# APU.net
KiCad netlist of a schematic drawn in EAGLE
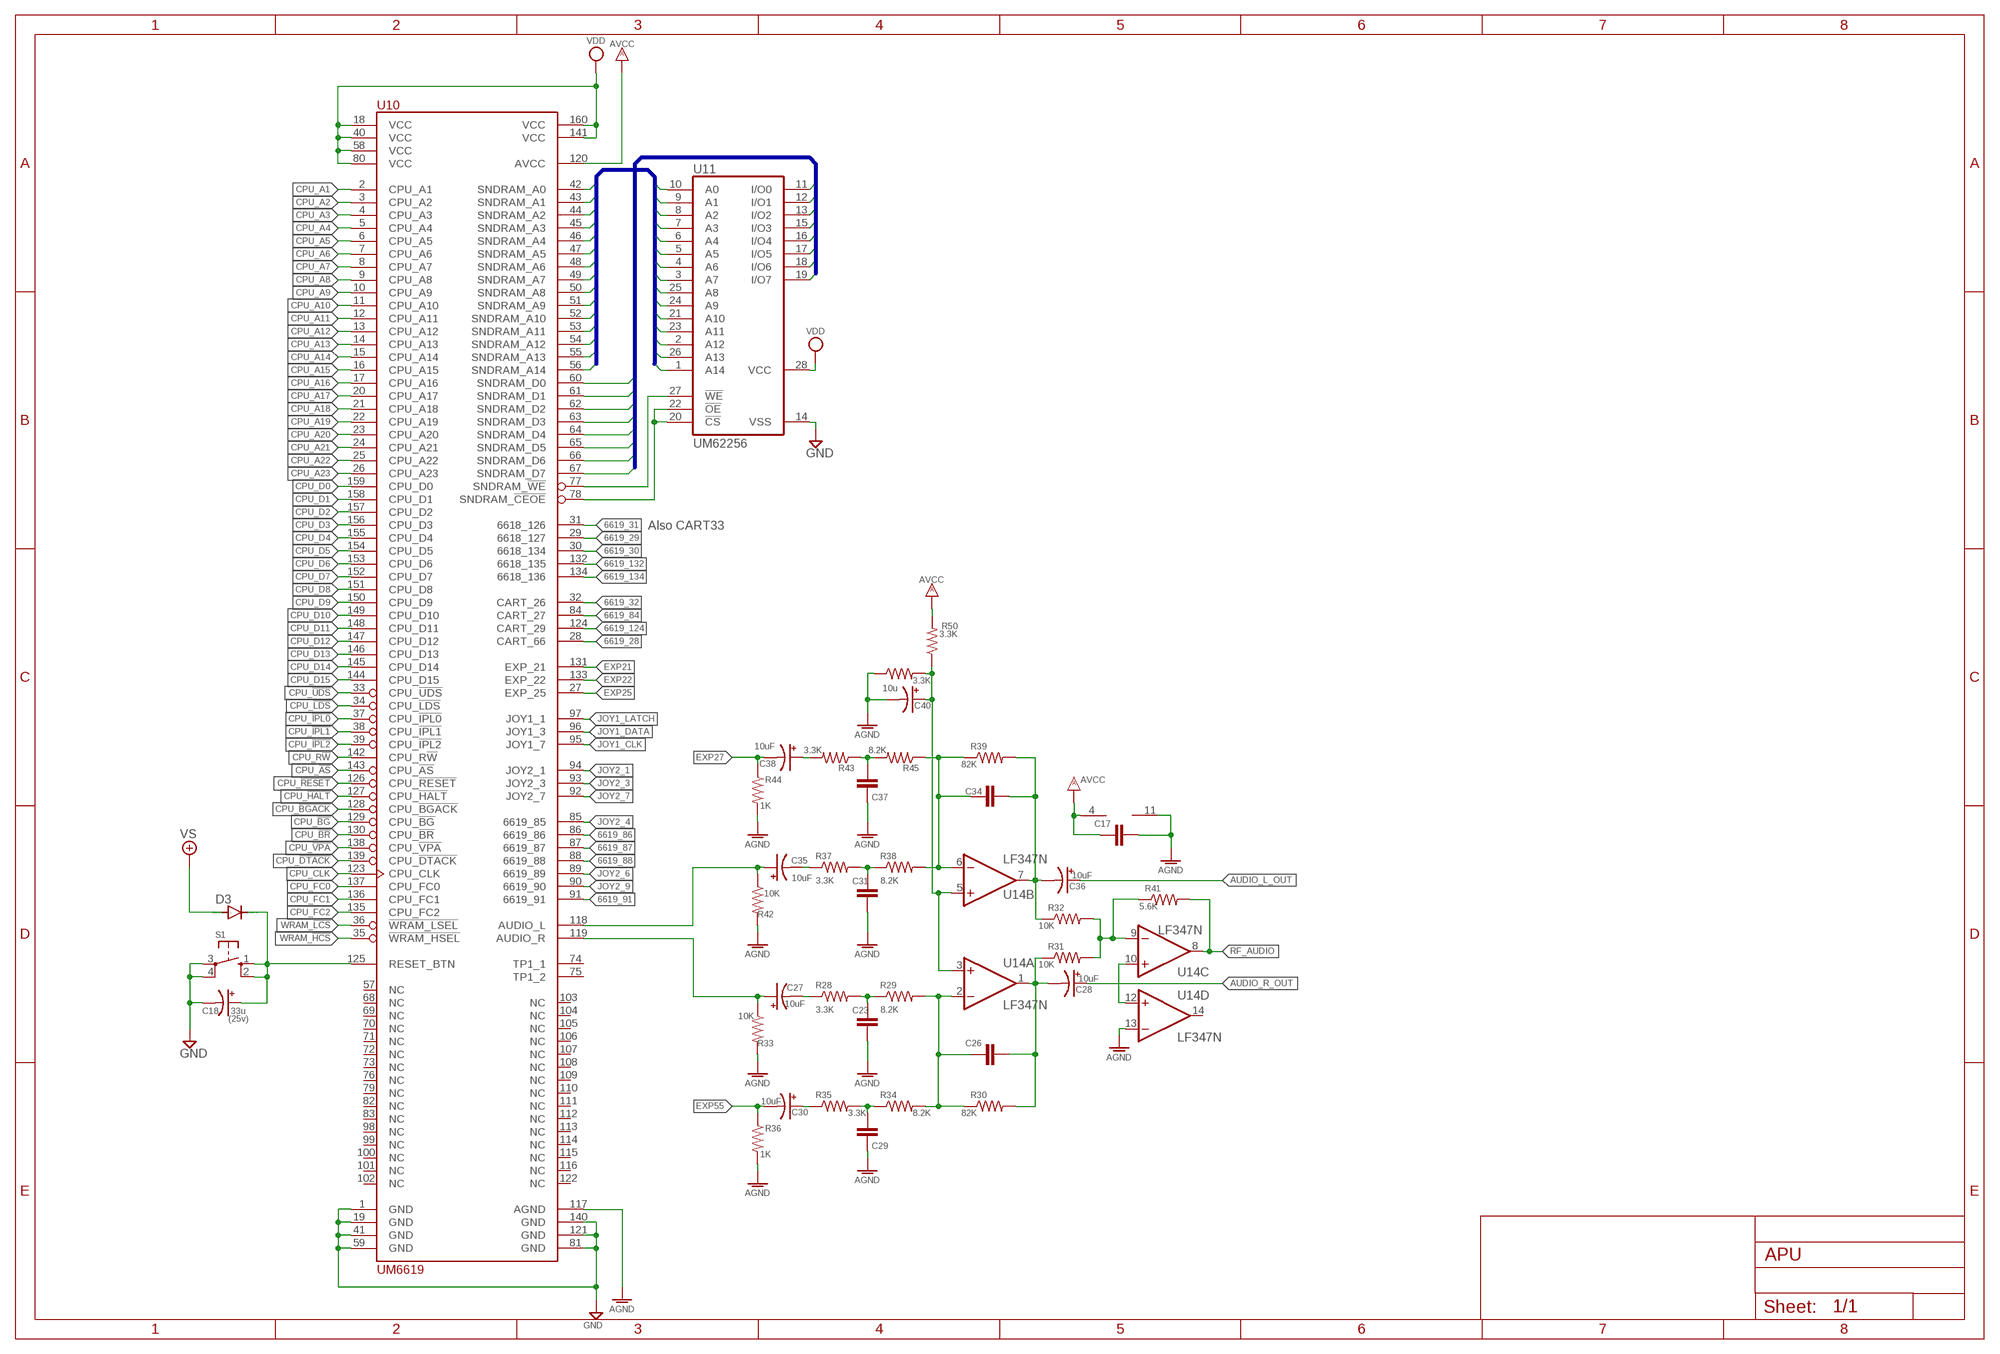
[diagram p0: schematic, sheet 1]

(export (version "E")
  (design (tool "Eeschema 10.0.6"))
  (components
    (comp (ref "C17")
      (value "C-EUC0805")
      (footprint "eagle-import:C0805")
      (libsource (lib "eagle-import") (part "C-EUC0805"))
    )
    (comp (ref "C18")
      (value "33u")
      (footprint "eagle-import:E2,5-5")
      (libsource (lib "eagle-import") (part "CPOL-USE2.5-5"))
    )
    (comp (ref "C23")
      (value "C-EUC0805")
      (footprint "eagle-import:C0805")
      (libsource (lib "eagle-import") (part "C-EUC0805"))
    )
    (comp (ref "C26")
      (value "C-EUC0805")
      (footprint "eagle-import:C0805")
      (libsource (lib "eagle-import") (part "C-EUC0805"))
    )
    (comp (ref "C27")
      (value "10uF")
      (footprint "eagle-import:TAP5-50")
      (libsource (lib "eagle-import") (part "CPOL-USTAP5-50"))
    )
    (comp (ref "C28")
      (value "10uF")
      (footprint "eagle-import:TAP5-50")
      (libsource (lib "eagle-import") (part "CPOL-USTAP5-50"))
    )
    (comp (ref "C29")
      (value "C-EUC0805")
      (footprint "eagle-import:C0805")
      (libsource (lib "eagle-import") (part "C-EUC0805"))
    )
    (comp (ref "C30")
      (value "10uF")
      (footprint "eagle-import:TAP5-50")
      (libsource (lib "eagle-import") (part "CPOL-USTAP5-50"))
    )
    (comp (ref "C31")
      (value "C-EUC0805")
      (footprint "eagle-import:C0805")
      (libsource (lib "eagle-import") (part "C-EUC0805"))
    )
    (comp (ref "C34")
      (value "C-EUC0805")
      (footprint "eagle-import:C0805")
      (libsource (lib "eagle-import") (part "C-EUC0805"))
    )
    (comp (ref "C35")
      (value "10uF")
      (footprint "eagle-import:TAP5-50")
      (libsource (lib "eagle-import") (part "CPOL-USTAP5-50"))
    )
    (comp (ref "C36")
      (value "10uF")
      (footprint "eagle-import:TAP5-50")
      (libsource (lib "eagle-import") (part "CPOL-USTAP5-50"))
    )
    (comp (ref "C37")
      (value "C-EUC0805")
      (footprint "eagle-import:C0805")
      (libsource (lib "eagle-import") (part "C-EUC0805"))
    )
    (comp (ref "C38")
      (value "10uF")
      (footprint "eagle-import:TAP5-50")
      (libsource (lib "eagle-import") (part "CPOL-USTAP5-50"))
    )
    (comp (ref "C40")
      (value "10u")
      (footprint "eagle-import:TAP5-50")
      (libsource (lib "eagle-import") (part "CPOL-USTAP5-50"))
    )
    (comp (ref "D3")
      (value "DIODE-SOD80C")
      (footprint "eagle-import:SOD80C")
      (libsource (lib "eagle-import") (part "DIODE-SOD80C"))
    )
    (comp (ref "R28")
      (value "3.3K")
      (footprint "eagle-import:R0805")
      (libsource (lib "eagle-import") (part "R-US_R0805"))
    )
    (comp (ref "R29")
      (value "8.2K")
      (footprint "eagle-import:R0805")
      (libsource (lib "eagle-import") (part "R-US_R0805"))
    )
    (comp (ref "R30")
      (value "82K")
      (footprint "eagle-import:R0805")
      (libsource (lib "eagle-import") (part "R-US_R0805"))
    )
    (comp (ref "R31")
      (value "10K")
      (footprint "eagle-import:R0805")
      (libsource (lib "eagle-import") (part "R-US_R0805"))
    )
    (comp (ref "R32")
      (value "10K")
      (footprint "eagle-import:R0805")
      (libsource (lib "eagle-import") (part "R-US_R0805"))
    )
    (comp (ref "R33")
      (value "10K")
      (footprint "eagle-import:R0805")
      (libsource (lib "eagle-import") (part "R-US_R0805"))
    )
    (comp (ref "R34")
      (value "8.2K")
      (footprint "eagle-import:R0805")
      (libsource (lib "eagle-import") (part "R-US_R0805"))
    )
    (comp (ref "R35")
      (value "3.3K")
      (footprint "eagle-import:R0805")
      (libsource (lib "eagle-import") (part "R-US_R0805"))
    )
    (comp (ref "R36")
      (value "1K")
      (footprint "eagle-import:R0805")
      (libsource (lib "eagle-import") (part "R-US_R0805"))
    )
    (comp (ref "R37")
      (value "3.3K")
      (footprint "eagle-import:R0805")
      (libsource (lib "eagle-import") (part "R-US_R0805"))
    )
    (comp (ref "R38")
      (value "8.2K")
      (footprint "eagle-import:R0805")
      (libsource (lib "eagle-import") (part "R-US_R0805"))
    )
    (comp (ref "R39")
      (value "82K")
      (footprint "eagle-import:R0805")
      (libsource (lib "eagle-import") (part "R-US_R0805"))
    )
    (comp (ref "R41")
      (value "5.6K")
      (footprint "eagle-import:R0805")
      (libsource (lib "eagle-import") (part "R-US_R0805"))
    )
    (comp (ref "R42")
      (value "10K")
      (footprint "eagle-import:R0805")
      (libsource (lib "eagle-import") (part "R-US_R0805"))
    )
    (comp (ref "R43")
      (value "3.3K")
      (footprint "eagle-import:R0805")
      (libsource (lib "eagle-import") (part "R-US_R0805"))
    )
    (comp (ref "R44")
      (value "1K")
      (footprint "eagle-import:R0805")
      (libsource (lib "eagle-import") (part "R-US_R0805"))
    )
    (comp (ref "R45")
      (value "8.2K")
      (footprint "eagle-import:R0805")
      (libsource (lib "eagle-import") (part "R-US_R0805"))
    )
    (comp (ref "R49")
      (value "3.3K")
      (footprint "eagle-import:R0805")
      (libsource (lib "eagle-import") (part "R-US_R0805"))
    )
    (comp (ref "R50")
      (value "3.3K")
      (footprint "eagle-import:R0805")
      (libsource (lib "eagle-import") (part "R-US_R0805"))
    )
    (comp (ref "S1")
      (value "40-XX")
      (footprint "eagle-import:B3F-40XX")
      (fields (field (name "MF") "OMRON COMPONENTS USA") (field (name "MPN") "B3F-4000"))
      (libsource (lib "eagle-import") (part "40-XX"))
    )
    (comp (ref "U10")
      (value "UM6619")
      (footprint "eagle-import:QFP160")
      (libsource (lib "eagle-import") (part "UM6619"))
    )
    (comp (ref "U11")
      (value "UM62256")
      (footprint "eagle-import:SO28L")
      (fields (field (name "MPN") "CY62256VNLL-70SNXI"))
      (libsource (lib "eagle-import") (part "62256FP"))
    )
    (comp (ref "U14")
      (value "LF347N")
      (footprint "eagle-import:DIL14")
      (libsource (lib "eagle-import") (part "LF347N"))
    )
  )
  (nets
    (net (code "1") (name "/CPU_R~{W}") (class "Default")
      (node (ref "U10") (pin "142") (pinfunction "CPU_R~{W}_142") (pintype "input"))
    )
    (net (code "2") (name "/CPU_~{AS}") (class "Default")
      (node (ref "U10") (pin "143") (pinfunction "CPU_~{AS}_143") (pintype "input"))
    )
    (net (code "3") (name "/CPU_~{BGACK}") (class "Default")
      (node (ref "U10") (pin "128") (pinfunction "CPU_~{BGACK}_128") (pintype "output"))
    )
    (net (code "4") (name "/CPU_~{BG}") (class "Default")
      (node (ref "U10") (pin "129") (pinfunction "CPU_~{BG}_129") (pintype "input"))
    )
    (net (code "5") (name "/CPU_~{BR}") (class "Default")
      (node (ref "U10") (pin "130") (pinfunction "CPU_~{BR}_130") (pintype "output"))
    )
    (net (code "6") (name "/CPU_~{DTACK}") (class "Default")
      (node (ref "U10") (pin "139") (pinfunction "CPU_~{DTACK}_139") (pintype "output"))
    )
    (net (code "7") (name "/CPU_~{HALT}") (class "Default")
      (node (ref "U10") (pin "127") (pinfunction "CPU_~{HALT}_127") (pintype "bidirectional"))
    )
    (net (code "8") (name "/CPU_~{IPL0}") (class "Default")
      (node (ref "U10") (pin "37") (pinfunction "CPU_~{IPL0}_37") (pintype "input"))
    )
    (net (code "9") (name "/CPU_~{IPL1}") (class "Default")
      (node (ref "U10") (pin "38") (pinfunction "CPU_~{IPL1}_38") (pintype "input"))
    )
    (net (code "10") (name "/CPU_~{IPL2}") (class "Default")
      (node (ref "U10") (pin "39") (pinfunction "CPU_~{IPL2}_39") (pintype "input"))
    )
    (net (code "11") (name "/CPU_~{LDS}") (class "Default")
      (node (ref "U10") (pin "34") (pinfunction "CPU_~{LDS}_34") (pintype "input"))
    )
    (net (code "12") (name "/CPU_~{RESET}") (class "Default")
      (node (ref "U10") (pin "126") (pinfunction "CPU_~{RESET}_126") (pintype "bidirectional"))
    )
    (net (code "13") (name "/CPU_~{UDS}") (class "Default")
      (node (ref "U10") (pin "33") (pinfunction "CPU_~{UDS}_33") (pintype "input"))
    )
    (net (code "14") (name "/CPU_~{VPA}") (class "Default")
      (node (ref "U10") (pin "138") (pinfunction "CPU_~{VPA}_138") (pintype "output"))
    )
    (net (code "15") (name "/SNDRAM_A0") (class "Default")
      (node (ref "U10") (pin "42") (pinfunction "SNDRAM_A0_42") (pintype "output"))
      (node (ref "U11") (pin "10") (pinfunction "A0_10") (pintype "input"))
    )
    (net (code "16") (name "/SNDRAM_A1") (class "Default")
      (node (ref "U10") (pin "43") (pinfunction "SNDRAM_A1_43") (pintype "output"))
      (node (ref "U11") (pin "9") (pinfunction "A1_9") (pintype "input"))
    )
    (net (code "17") (name "/SNDRAM_A2") (class "Default")
      (node (ref "U10") (pin "44") (pinfunction "SNDRAM_A2_44") (pintype "output"))
      (node (ref "U11") (pin "8") (pinfunction "A2_8") (pintype "input"))
    )
    (net (code "18") (name "/SNDRAM_A3") (class "Default")
      (node (ref "U10") (pin "45") (pinfunction "SNDRAM_A3_45") (pintype "output"))
      (node (ref "U11") (pin "7") (pinfunction "A3_7") (pintype "input"))
    )
    (net (code "19") (name "/SNDRAM_A4") (class "Default")
      (node (ref "U10") (pin "46") (pinfunction "SNDRAM_A4_46") (pintype "output"))
      (node (ref "U11") (pin "6") (pinfunction "A4_6") (pintype "input"))
    )
    (net (code "20") (name "/SNDRAM_A5") (class "Default")
      (node (ref "U10") (pin "47") (pinfunction "SNDRAM_A5_47") (pintype "output"))
      (node (ref "U11") (pin "5") (pinfunction "A5_5") (pintype "input"))
    )
    (net (code "21") (name "/SNDRAM_A6") (class "Default")
      (node (ref "U10") (pin "48") (pinfunction "SNDRAM_A6_48") (pintype "output"))
      (node (ref "U11") (pin "4") (pinfunction "A6_4") (pintype "input"))
    )
    (net (code "22") (name "/SNDRAM_A7") (class "Default")
      (node (ref "U10") (pin "49") (pinfunction "SNDRAM_A7_49") (pintype "output"))
      (node (ref "U11") (pin "3") (pinfunction "A7_3") (pintype "input"))
    )
    (net (code "23") (name "/SNDRAM_A8") (class "Default")
      (node (ref "U10") (pin "50") (pinfunction "SNDRAM_A8_50") (pintype "output"))
      (node (ref "U11") (pin "25") (pinfunction "A8_25") (pintype "input"))
    )
    (net (code "24") (name "/SNDRAM_A9") (class "Default")
      (node (ref "U10") (pin "51") (pinfunction "SNDRAM_A9_51") (pintype "output"))
      (node (ref "U11") (pin "24") (pinfunction "A9_24") (pintype "input"))
    )
    (net (code "25") (name "/SNDRAM_A10") (class "Default")
      (node (ref "U10") (pin "52") (pinfunction "SNDRAM_A10_52") (pintype "output"))
      (node (ref "U11") (pin "21") (pinfunction "A10_21") (pintype "input"))
    )
    (net (code "26") (name "/SNDRAM_A11") (class "Default")
      (node (ref "U10") (pin "53") (pinfunction "SNDRAM_A11_53") (pintype "output"))
      (node (ref "U11") (pin "23") (pinfunction "A11_23") (pintype "input"))
    )
    (net (code "27") (name "/SNDRAM_A12") (class "Default")
      (node (ref "U10") (pin "54") (pinfunction "SNDRAM_A12_54") (pintype "output"))
      (node (ref "U11") (pin "2") (pinfunction "A12_2") (pintype "input"))
    )
    (net (code "28") (name "/SNDRAM_A13") (class "Default")
      (node (ref "U10") (pin "55") (pinfunction "SNDRAM_A13_55") (pintype "output"))
      (node (ref "U11") (pin "26") (pinfunction "A13_26") (pintype "input"))
    )
    (net (code "29") (name "/SNDRAM_A14") (class "Default")
      (node (ref "U10") (pin "56") (pinfunction "SNDRAM_A14_56") (pintype "output"))
      (node (ref "U11") (pin "1") (pinfunction "A14_1") (pintype "input"))
    )
    (net (code "30") (name "/SNDRAM_D0") (class "Default")
      (node (ref "U10") (pin "60") (pinfunction "SNDRAM_D0_60") (pintype "open_collector"))
      (node (ref "U11") (pin "11") (pinfunction "I/O0_11") (pintype "bidirectional"))
    )
    (net (code "31") (name "/SNDRAM_D1") (class "Default")
      (node (ref "U10") (pin "61") (pinfunction "SNDRAM_D1_61") (pintype "bidirectional"))
      (node (ref "U11") (pin "12") (pinfunction "I/O1_12") (pintype "bidirectional"))
    )
    (net (code "32") (name "/SNDRAM_D2") (class "Default")
      (node (ref "U10") (pin "62") (pinfunction "SNDRAM_D2_62") (pintype "bidirectional"))
      (node (ref "U11") (pin "13") (pinfunction "I/O2_13") (pintype "bidirectional"))
    )
    (net (code "33") (name "/SNDRAM_D3") (class "Default")
      (node (ref "U10") (pin "63") (pinfunction "SNDRAM_D3_63") (pintype "bidirectional"))
      (node (ref "U11") (pin "15") (pinfunction "I/O3_15") (pintype "bidirectional"))
    )
    (net (code "34") (name "/SNDRAM_D4") (class "Default")
      (node (ref "U10") (pin "64") (pinfunction "SNDRAM_D4_64") (pintype "bidirectional"))
      (node (ref "U11") (pin "16") (pinfunction "I/O4_16") (pintype "bidirectional"))
    )
    (net (code "35") (name "/SNDRAM_D5") (class "Default")
      (node (ref "U10") (pin "65") (pinfunction "SNDRAM_D5_65") (pintype "bidirectional"))
      (node (ref "U11") (pin "17") (pinfunction "I/O5_17") (pintype "bidirectional"))
    )
    (net (code "36") (name "/SNDRAM_D6") (class "Default")
      (node (ref "U10") (pin "66") (pinfunction "SNDRAM_D6_66") (pintype "bidirectional"))
      (node (ref "U11") (pin "18") (pinfunction "I/O6_18") (pintype "bidirectional"))
    )
    (net (code "37") (name "/SNDRAM_D7") (class "Default")
      (node (ref "U10") (pin "67") (pinfunction "SNDRAM_D7_67") (pintype "bidirectional"))
      (node (ref "U11") (pin "19") (pinfunction "I/O7_19") (pintype "bidirectional"))
    )
    (net (code "38") (name "/WRAM_~{HCS}") (class "Default")
      (node (ref "U10") (pin "35") (pinfunction "~{WRAM_HSEL}_35") (pintype "output"))
    )
    (net (code "39") (name "/WRAM_~{LCS}") (class "Default")
      (node (ref "U10") (pin "36") (pinfunction "~{WRAM_LSEL}_36") (pintype "output"))
    )
    (net (code "40") (name "6619_28") (class "Default")
      (node (ref "U10") (pin "28") (pinfunction "CART_66_28") (pintype "bidirectional"))
    )
    (net (code "41") (name "6619_29") (class "Default")
      (node (ref "U10") (pin "29") (pinfunction "6618_127_29") (pintype "bidirectional"))
    )
    (net (code "42") (name "6619_30") (class "Default")
      (node (ref "U10") (pin "30") (pinfunction "6618_134_30") (pintype "bidirectional"))
    )
    (net (code "43") (name "6619_31") (class "Default")
      (node (ref "U10") (pin "31") (pinfunction "6618_126_31") (pintype "bidirectional"))
    )
    (net (code "44") (name "6619_32") (class "Default")
      (node (ref "U10") (pin "32") (pinfunction "CART_26_32") (pintype "bidirectional"))
    )
    (net (code "45") (name "6619_84") (class "Default")
      (node (ref "U10") (pin "84") (pinfunction "CART_27_84") (pintype "bidirectional"))
    )
    (net (code "46") (name "6619_86") (class "Default")
      (node (ref "U10") (pin "86") (pinfunction "6619_86_86") (pintype "output"))
    )
    (net (code "47") (name "6619_87") (class "Default")
      (node (ref "U10") (pin "87") (pinfunction "6619_87_87") (pintype "output"))
    )
    (net (code "48") (name "6619_88") (class "Default")
      (node (ref "U10") (pin "88") (pinfunction "6619_88_88") (pintype "output"))
    )
    (net (code "49") (name "6619_91") (class "Default")
      (node (ref "U10") (pin "91") (pinfunction "6619_91_91") (pintype "output"))
    )
    (net (code "50") (name "6619_124") (class "Default")
      (node (ref "U10") (pin "124") (pinfunction "CART_29_124") (pintype "input"))
    )
    (net (code "51") (name "6619_132") (class "Default")
      (node (ref "U10") (pin "132") (pinfunction "6618_135_132") (pintype "bidirectional"))
    )
    (net (code "52") (name "6619_134") (class "Default")
      (node (ref "U10") (pin "134") (pinfunction "6618_136_134") (pintype "bidirectional"))
    )
    (net (code "53") (name "AGND") (class "Default")
      (node (ref "C17") (pin "2") (pinfunction "2_2") (pintype "passive"))
      (node (ref "C23") (pin "2") (pinfunction "2_2") (pintype "passive"))
      (node (ref "C29") (pin "2") (pinfunction "2_2") (pintype "passive"))
      (node (ref "C31") (pin "2") (pinfunction "2_2") (pintype "passive"))
      (node (ref "C37") (pin "2") (pinfunction "2_2") (pintype "passive"))
      (node (ref "C40") (pin "-") (pinfunction "-_-") (pintype "passive"))
      (node (ref "R33") (pin "2") (pinfunction "2_2") (pintype "passive"))
      (node (ref "R36") (pin "2") (pinfunction "2_2") (pintype "passive"))
      (node (ref "R42") (pin "2") (pinfunction "2_2") (pintype "passive"))
      (node (ref "R44") (pin "2") (pinfunction "2_2") (pintype "passive"))
      (node (ref "R49") (pin "1") (pinfunction "1_1") (pintype "passive"))
      (node (ref "U10") (pin "117") (pinfunction "AGND_117") (pintype "power_in"))
      (node (ref "U14") (pin "11") (pinfunction "V-_11") (pintype "power_in"))
      (node (ref "U14") (pin "13") (pinfunction "-IN_13") (pintype "input"))
    )
    (net (code "54") (name "AUDIO_L_OUT") (class "Default")
      (node (ref "C36") (pin "+") (pinfunction "+_+") (pintype "passive"))
    )
    (net (code "55") (name "AUDIO_R_OUT") (class "Default")
      (node (ref "C28") (pin "+") (pinfunction "+_+") (pintype "passive"))
    )
    (net (code "56") (name "AVCC") (class "Default")
      (node (ref "C17") (pin "1") (pinfunction "1_1") (pintype "passive"))
      (node (ref "R50") (pin "2") (pinfunction "2_2") (pintype "passive"))
      (node (ref "U10") (pin "120") (pinfunction "AVCC_120") (pintype "power_in"))
      (node (ref "U14") (pin "4") (pinfunction "V+_4") (pintype "power_in"))
    )
    (net (code "57") (name "CPU_A1") (class "Default")
      (node (ref "U10") (pin "2") (pinfunction "CPU_A1_2") (pintype "input"))
    )
    (net (code "58") (name "CPU_A2") (class "Default")
      (node (ref "U10") (pin "3") (pinfunction "CPU_A2_3") (pintype "output"))
    )
    (net (code "59") (name "CPU_A3") (class "Default")
      (node (ref "U10") (pin "4") (pinfunction "CPU_A3_4") (pintype "input"))
    )
    (net (code "60") (name "CPU_A4") (class "Default")
      (node (ref "U10") (pin "5") (pinfunction "CPU_A4_5") (pintype "input"))
    )
    (net (code "61") (name "CPU_A5") (class "Default")
      (node (ref "U10") (pin "6") (pinfunction "CPU_A5_6") (pintype "input"))
    )
    (net (code "62") (name "CPU_A6") (class "Default")
      (node (ref "U10") (pin "7") (pinfunction "CPU_A6_7") (pintype "input"))
    )
    (net (code "63") (name "CPU_A7") (class "Default")
      (node (ref "U10") (pin "8") (pinfunction "CPU_A7_8") (pintype "input"))
    )
    (net (code "64") (name "CPU_A8") (class "Default")
      (node (ref "U10") (pin "9") (pinfunction "CPU_A8_9") (pintype "input"))
    )
    (net (code "65") (name "CPU_A9") (class "Default")
      (node (ref "U10") (pin "10") (pinfunction "CPU_A9_10") (pintype "input"))
    )
    (net (code "66") (name "CPU_A10") (class "Default")
      (node (ref "U10") (pin "11") (pinfunction "CPU_A10_11") (pintype "input"))
    )
    (net (code "67") (name "CPU_A11") (class "Default")
      (node (ref "U10") (pin "12") (pinfunction "CPU_A11_12") (pintype "input"))
    )
    (net (code "68") (name "CPU_A12") (class "Default")
      (node (ref "U10") (pin "13") (pinfunction "CPU_A12_13") (pintype "input"))
    )
    (net (code "69") (name "CPU_A13") (class "Default")
      (node (ref "U10") (pin "14") (pinfunction "CPU_A13_14") (pintype "input"))
    )
    (net (code "70") (name "CPU_A14") (class "Default")
      (node (ref "U10") (pin "15") (pinfunction "CPU_A14_15") (pintype "input"))
    )
    (net (code "71") (name "CPU_A15") (class "Default")
      (node (ref "U10") (pin "16") (pinfunction "CPU_A15_16") (pintype "input"))
    )
    (net (code "72") (name "CPU_A16") (class "Default")
      (node (ref "U10") (pin "17") (pinfunction "CPU_A16_17") (pintype "input"))
    )
    (net (code "73") (name "CPU_A17") (class "Default")
      (node (ref "U10") (pin "20") (pinfunction "CPU_A17_20") (pintype "input"))
    )
    (net (code "74") (name "CPU_A18") (class "Default")
      (node (ref "U10") (pin "21") (pinfunction "CPU_A18_21") (pintype "bidirectional"))
    )
    (net (code "75") (name "CPU_A19") (class "Default")
      (node (ref "U10") (pin "22") (pinfunction "CPU_A19_22") (pintype "input"))
    )
    (net (code "76") (name "CPU_A20") (class "Default")
      (node (ref "U10") (pin "23") (pinfunction "CPU_A20_23") (pintype "input"))
    )
    (net (code "77") (name "CPU_A21") (class "Default")
      (node (ref "U10") (pin "24") (pinfunction "CPU_A21_24") (pintype "input"))
    )
    (net (code "78") (name "CPU_A22") (class "Default")
      (node (ref "U10") (pin "25") (pinfunction "CPU_A22_25") (pintype "input"))
    )
    (net (code "79") (name "CPU_A23") (class "Default")
      (node (ref "U10") (pin "26") (pinfunction "CPU_A23_26") (pintype "input"))
    )
    (net (code "80") (name "CPU_CLK") (class "Default")
      (node (ref "U10") (pin "123") (pinfunction "CPU_CLK_123") (pintype "output"))
    )
    (net (code "81") (name "CPU_D0") (class "Default")
      (node (ref "U10") (pin "159") (pinfunction "CPU_D0_159") (pintype "bidirectional"))
    )
    (net (code "82") (name "CPU_D1") (class "Default")
      (node (ref "U10") (pin "158") (pinfunction "CPU_D1_158") (pintype "bidirectional"))
    )
    (net (code "83") (name "CPU_D2") (class "Default")
      (node (ref "U10") (pin "157") (pinfunction "CPU_D2_157") (pintype "bidirectional"))
    )
    (net (code "84") (name "CPU_D3") (class "Default")
      (node (ref "U10") (pin "156") (pinfunction "CPU_D3_156") (pintype "bidirectional"))
    )
    (net (code "85") (name "CPU_D4") (class "Default")
      (node (ref "U10") (pin "155") (pinfunction "CPU_D4_155") (pintype "bidirectional"))
    )
    (net (code "86") (name "CPU_D5") (class "Default")
      (node (ref "U10") (pin "154") (pinfunction "CPU_D5_154") (pintype "bidirectional"))
    )
    (net (code "87") (name "CPU_D6") (class "Default")
      (node (ref "U10") (pin "153") (pinfunction "CPU_D6_153") (pintype "bidirectional"))
    )
    (net (code "88") (name "CPU_D7") (class "Default")
      (node (ref "U10") (pin "152") (pinfunction "CPU_D7_152") (pintype "bidirectional"))
    )
    (net (code "89") (name "CPU_D8") (class "Default")
      (node (ref "U10") (pin "151") (pinfunction "CPU_D8_151") (pintype "bidirectional"))
    )
    (net (code "90") (name "CPU_D9") (class "Default")
      (node (ref "U10") (pin "150") (pinfunction "CPU_D9_150") (pintype "bidirectional"))
    )
    (net (code "91") (name "CPU_D10") (class "Default")
      (node (ref "U10") (pin "149") (pinfunction "CPU_D10_149") (pintype "bidirectional"))
    )
    (net (code "92") (name "CPU_D11") (class "Default")
      (node (ref "U10") (pin "148") (pinfunction "CPU_D11_148") (pintype "bidirectional"))
    )
    (net (code "93") (name "CPU_D12") (class "Default")
      (node (ref "U10") (pin "147") (pinfunction "CPU_D12_147") (pintype "bidirectional"))
    )
    (net (code "94") (name "CPU_D13") (class "Default")
      (node (ref "U10") (pin "146") (pinfunction "CPU_D13_146") (pintype "bidirectional"))
    )
    (net (code "95") (name "CPU_D14") (class "Default")
      (node (ref "U10") (pin "145") (pinfunction "CPU_D14_145") (pintype "bidirectional"))
    )
    (net (code "96") (name "CPU_D15") (class "Default")
      (node (ref "U10") (pin "144") (pinfunction "CPU_D15_144") (pintype "bidirectional"))
    )
    (net (code "97") (name "CPU_FC0") (class "Default")
      (node (ref "U10") (pin "137") (pinfunction "CPU_FC0_137") (pintype "input"))
    )
    (net (code "98") (name "CPU_FC1") (class "Default")
      (node (ref "U10") (pin "136") (pinfunction "CPU_FC1_136") (pintype "input"))
    )
    (net (code "99") (name "CPU_FC2") (class "Default")
      (node (ref "U10") (pin "135") (pinfunction "CPU_FC2_135") (pintype "input"))
    )
    (net (code "100") (name "EXP21") (class "Default")
      (node (ref "U10") (pin "131") (pinfunction "EXP_21_131") (pintype "bidirectional"))
    )
    (net (code "101") (name "EXP22") (class "Default")
      (node (ref "U10") (pin "133") (pinfunction "EXP_22_133") (pintype "bidirectional"))
    )
    (net (code "102") (name "EXP25") (class "Default")
      (node (ref "U10") (pin "27") (pinfunction "EXP_25_27") (pintype "bidirectional"))
    )
    (net (code "103") (name "EXP27") (class "Default")
      (node (ref "C38") (pin "-") (pinfunction "-_-") (pintype "passive"))
      (node (ref "R44") (pin "1") (pinfunction "1_1") (pintype "passive"))
    )
    (net (code "104") (name "EXP55") (class "Default")
      (node (ref "C30") (pin "-") (pinfunction "-_-") (pintype "passive"))
      (node (ref "R36") (pin "1") (pinfunction "1_1") (pintype "passive"))
    )
    (net (code "105") (name "GND") (class "Default")
      (node (ref "C18") (pin "-") (pinfunction "-_-") (pintype "passive"))
      (node (ref "S1") (pin "3") (pinfunction "P_3") (pintype "passive"))
      (node (ref "S1") (pin "4") (pinfunction "P1_4") (pintype "passive"))
      (node (ref "U10") (pin "1") (pinfunction "GND_1") (pintype "power_in"))
      (node (ref "U10") (pin "121") (pinfunction "GND_121") (pintype "power_in"))
      (node (ref "U10") (pin "140") (pinfunction "GND_140") (pintype "power_in"))
      (node (ref "U10") (pin "19") (pinfunction "GND_19") (pintype "power_in"))
      (node (ref "U10") (pin "41") (pinfunction "GND_41") (pintype "power_in"))
      (node (ref "U10") (pin "59") (pinfunction "GND_59") (pintype "power_in"))
      (node (ref "U10") (pin "81") (pinfunction "GND_81") (pintype "power_in"))
      (node (ref "U11") (pin "14") (pinfunction "VSS_14") (pintype "power_in"))
    )
    (net (code "106") (name "JOY1_CLK") (class "Default")
      (node (ref "U10") (pin "95") (pinfunction "JOY1_7_95") (pintype "bidirectional"))
    )
    (net (code "107") (name "JOY1_DATA") (class "Default")
      (node (ref "U10") (pin "96") (pinfunction "JOY1_3_96") (pintype "bidirectional"))
    )
    (net (code "108") (name "JOY1_LATCH") (class "Default")
      (node (ref "U10") (pin "97") (pinfunction "JOY1_1_97") (pintype "bidirectional"))
    )
    (net (code "109") (name "JOY2_1") (class "Default")
      (node (ref "U10") (pin "94") (pinfunction "JOY2_1_94") (pintype "bidirectional"))
    )
    (net (code "110") (name "JOY2_3") (class "Default")
      (node (ref "U10") (pin "93") (pinfunction "JOY2_3_93") (pintype "bidirectional"))
    )
    (net (code "111") (name "JOY2_4") (class "Default")
      (node (ref "U10") (pin "85") (pinfunction "6619_85_85") (pintype "output"))
    )
    (net (code "112") (name "JOY2_6") (class "Default")
      (node (ref "U10") (pin "89") (pinfunction "6619_89_89") (pintype "output"))
    )
    (net (code "113") (name "JOY2_7") (class "Default")
      (node (ref "U10") (pin "92") (pinfunction "JOY2_7_92") (pintype "bidirectional"))
    )
    (net (code "114") (name "JOY2_9") (class "Default")
      (node (ref "U10") (pin "90") (pinfunction "6619_90_90") (pintype "output"))
    )
    (net (code "115") (name "Net-(C23-Pad1)") (class "Default")
      (node (ref "C23") (pin "1") (pinfunction "1_1") (pintype "passive"))
      (node (ref "R28") (pin "2") (pinfunction "2_2") (pintype "passive"))
      (node (ref "R29") (pin "1") (pinfunction "1_1") (pintype "passive"))
    )
    (net (code "116") (name "Net-(C27-Pad-)") (class "Default")
      (node (ref "C27") (pin "-") (pinfunction "-_-") (pintype "passive"))
      (node (ref "R28") (pin "1") (pinfunction "1_1") (pintype "passive"))
    )
    (net (code "117") (name "Net-(C29-Pad1)") (class "Default")
      (node (ref "C29") (pin "1") (pinfunction "1_1") (pintype "passive"))
      (node (ref "R34") (pin "1") (pinfunction "1_1") (pintype "passive"))
      (node (ref "R35") (pin "2") (pinfunction "2_2") (pintype "passive"))
    )
    (net (code "118") (name "Net-(C30-Pad+)") (class "Default")
      (node (ref "C30") (pin "+") (pinfunction "+_+") (pintype "passive"))
      (node (ref "R35") (pin "1") (pinfunction "1_1") (pintype "passive"))
    )
    (net (code "119") (name "Net-(C31-Pad1)") (class "Default")
      (node (ref "C31") (pin "1") (pinfunction "1_1") (pintype "passive"))
      (node (ref "R37") (pin "2") (pinfunction "2_2") (pintype "passive"))
      (node (ref "R38") (pin "1") (pinfunction "1_1") (pintype "passive"))
    )
    (net (code "120") (name "Net-(C35-Pad-)") (class "Default")
      (node (ref "C35") (pin "-") (pinfunction "-_-") (pintype "passive"))
      (node (ref "R37") (pin "1") (pinfunction "1_1") (pintype "passive"))
    )
    (net (code "121") (name "Net-(C37-Pad1)") (class "Default")
      (node (ref "C37") (pin "1") (pinfunction "1_1") (pintype "passive"))
      (node (ref "R43") (pin "1") (pinfunction "1_1") (pintype "passive"))
      (node (ref "R45") (pin "2") (pinfunction "2_2") (pintype "passive"))
    )
    (net (code "122") (name "Net-(C38-Pad+)") (class "Default")
      (node (ref "C38") (pin "+") (pinfunction "+_+") (pintype "passive"))
      (node (ref "R43") (pin "2") (pinfunction "2_2") (pintype "passive"))
    )
    (net (code "123") (name "Net-(S1-S)") (class "Default")
      (node (ref "C18") (pin "+") (pinfunction "+_+") (pintype "passive"))
      (node (ref "D3") (pin "C") (pinfunction "C_C") (pintype "passive"))
      (node (ref "S1") (pin "1") (pinfunction "S_1") (pintype "passive"))
      (node (ref "S1") (pin "2") (pinfunction "S1_2") (pintype "passive"))
      (node (ref "U10") (pin "125") (pinfunction "RESET_BTN_125") (pintype "input"))
    )
    (net (code "124") (name "Net-(U10-AUDIO_L)") (class "Default")
      (node (ref "C35") (pin "+") (pinfunction "+_+") (pintype "passive"))
      (node (ref "R42") (pin "1") (pinfunction "1_1") (pintype "passive"))
      (node (ref "U10") (pin "118") (pinfunction "AUDIO_L_118") (pintype "output"))
    )
    (net (code "125") (name "Net-(U10-AUDIO_R)") (class "Default")
      (node (ref "C27") (pin "+") (pinfunction "+_+") (pintype "passive"))
      (node (ref "R33") (pin "1") (pinfunction "1_1") (pintype "passive"))
      (node (ref "U10") (pin "119") (pinfunction "AUDIO_R_119") (pintype "output"))
    )
    (net (code "126") (name "Net-(U10-SNDRAM_~{CEOE})") (class "Default")
      (node (ref "U10") (pin "78") (pinfunction "SNDRAM_~{CEOE}_78") (pintype "output"))
      (node (ref "U11") (pin "20") (pinfunction "~{CS}_20") (pintype "input"))
      (node (ref "U11") (pin "22") (pinfunction "~{OE}_22") (pintype "input"))
    )
    (net (code "127") (name "Net-(U10-SNDRAM_~{WE})") (class "Default")
      (node (ref "U10") (pin "77") (pinfunction "SNDRAM_~{WE}_77") (pintype "output"))
      (node (ref "U11") (pin "27") (pinfunction "~{WE}_27") (pintype "input"))
    )
    (net (code "128") (name "Net-(U14A-+IN)") (class "Default")
      (node (ref "C40") (pin "+") (pinfunction "+_+") (pintype "passive"))
      (node (ref "R49") (pin "2") (pinfunction "2_2") (pintype "passive"))
      (node (ref "R50") (pin "1") (pinfunction "1_1") (pintype "passive"))
      (node (ref "U14") (pin "3") (pinfunction "+IN_3") (pintype "input"))
      (node (ref "U14") (pin "5") (pinfunction "+IN_5") (pintype "input"))
    )
    (net (code "129") (name "Net-(U14A--IN)") (class "Default")
      (node (ref "C26") (pin "1") (pinfunction "1_1") (pintype "passive"))
      (node (ref "R29") (pin "2") (pinfunction "2_2") (pintype "passive"))
      (node (ref "R30") (pin "1") (pinfunction "1_1") (pintype "passive"))
      (node (ref "R34") (pin "2") (pinfunction "2_2") (pintype "passive"))
      (node (ref "U14") (pin "2") (pinfunction "-IN_2") (pintype "input"))
    )
    (net (code "130") (name "Net-(U14A-OUT)") (class "Default")
      (node (ref "C26") (pin "2") (pinfunction "2_2") (pintype "passive"))
      (node (ref "C28") (pin "-") (pinfunction "-_-") (pintype "passive"))
      (node (ref "R30") (pin "2") (pinfunction "2_2") (pintype "passive"))
      (node (ref "R31") (pin "1") (pinfunction "1_1") (pintype "passive"))
      (node (ref "U14") (pin "1") (pinfunction "OUT_1") (pintype "output"))
    )
    (net (code "131") (name "Net-(U14B--IN)") (class "Default")
      (node (ref "C34") (pin "1") (pinfunction "1_1") (pintype "passive"))
      (node (ref "R38") (pin "2") (pinfunction "2_2") (pintype "passive"))
      (node (ref "R39") (pin "1") (pinfunction "1_1") (pintype "passive"))
      (node (ref "R45") (pin "1") (pinfunction "1_1") (pintype "passive"))
      (node (ref "U14") (pin "6") (pinfunction "-IN_6") (pintype "input"))
    )
    (net (code "132") (name "Net-(U14B-OUT)") (class "Default")
      (node (ref "C34") (pin "2") (pinfunction "2_2") (pintype "passive"))
      (node (ref "C36") (pin "-") (pinfunction "-_-") (pintype "passive"))
      (node (ref "R32") (pin "1") (pinfunction "1_1") (pintype "passive"))
      (node (ref "R39") (pin "2") (pinfunction "2_2") (pintype "passive"))
      (node (ref "U14") (pin "7") (pinfunction "OUT_7") (pintype "output"))
    )
    (net (code "133") (name "Net-(U14C-+IN)") (class "Default")
      (node (ref "U14") (pin "10") (pinfunction "+IN_10") (pintype "input"))
      (node (ref "U14") (pin "12") (pinfunction "+IN_12") (pintype "input"))
    )
    (net (code "134") (name "Net-(U14C--IN)") (class "Default")
      (node (ref "R31") (pin "2") (pinfunction "2_2") (pintype "passive"))
      (node (ref "R32") (pin "2") (pinfunction "2_2") (pintype "passive"))
      (node (ref "R41") (pin "1") (pinfunction "1_1") (pintype "passive"))
      (node (ref "U14") (pin "9") (pinfunction "-IN_9") (pintype "input"))
    )
    (net (code "135") (name "RF_AUDIO") (class "Default")
      (node (ref "R41") (pin "2") (pinfunction "2_2") (pintype "passive"))
      (node (ref "U14") (pin "8") (pinfunction "OUT_8") (pintype "output"))
    )
    (net (code "136") (name "VDD") (class "Default")
      (node (ref "U10") (pin "141") (pinfunction "VCC_141") (pintype "power_in"))
      (node (ref "U10") (pin "160") (pinfunction "VCC_160") (pintype "power_in"))
      (node (ref "U10") (pin "18") (pinfunction "VCC_18") (pintype "power_in"))
      (node (ref "U10") (pin "40") (pinfunction "VCC_40") (pintype "power_in"))
      (node (ref "U10") (pin "58") (pinfunction "VCC_58") (pintype "power_in"))
      (node (ref "U10") (pin "80") (pinfunction "VCC_80") (pintype "power_in"))
      (node (ref "U11") (pin "28") (pinfunction "VCC_28") (pintype "power_in"))
    )
    (net (code "137") (name "VS") (class "Default")
      (node (ref "D3") (pin "A") (pinfunction "A_A") (pintype "passive"))
    )
    (net (code "138") (name "unconnected-(U10-NC-Pad57)") (class "Default")
      (node (ref "U10") (pin "57") (pinfunction "NC_57") (pintype "no_connect"))
    )
    (net (code "139") (name "unconnected-(U10-NC-Pad68)") (class "Default")
      (node (ref "U10") (pin "68") (pinfunction "NC_68") (pintype "no_connect"))
    )
    (net (code "140") (name "unconnected-(U10-NC-Pad69)") (class "Default")
      (node (ref "U10") (pin "69") (pinfunction "NC_69") (pintype "no_connect"))
    )
    (net (code "141") (name "unconnected-(U10-NC-Pad70)") (class "Default")
      (node (ref "U10") (pin "70") (pinfunction "NC_70") (pintype "no_connect"))
    )
    (net (code "142") (name "unconnected-(U10-NC-Pad71)") (class "Default")
      (node (ref "U10") (pin "71") (pinfunction "NC_71") (pintype "no_connect"))
    )
    (net (code "143") (name "unconnected-(U10-NC-Pad72)") (class "Default")
      (node (ref "U10") (pin "72") (pinfunction "NC_72") (pintype "no_connect"))
    )
    (net (code "144") (name "unconnected-(U10-NC-Pad73)") (class "Default")
      (node (ref "U10") (pin "73") (pinfunction "NC_73") (pintype "no_connect"))
    )
    (net (code "145") (name "unconnected-(U10-NC-Pad76)") (class "Default")
      (node (ref "U10") (pin "76") (pinfunction "NC_76") (pintype "no_connect"))
    )
    (net (code "146") (name "unconnected-(U10-NC-Pad79)") (class "Default")
      (node (ref "U10") (pin "79") (pinfunction "NC_79") (pintype "no_connect"))
    )
    (net (code "147") (name "unconnected-(U10-NC-Pad82)") (class "Default")
      (node (ref "U10") (pin "82") (pinfunction "NC_82") (pintype "no_connect"))
    )
    (net (code "148") (name "unconnected-(U10-NC-Pad83)") (class "Default")
      (node (ref "U10") (pin "83") (pinfunction "NC_83") (pintype "no_connect"))
    )
    (net (code "149") (name "unconnected-(U10-NC-Pad98)") (class "Default")
      (node (ref "U10") (pin "98") (pinfunction "NC_98") (pintype "no_connect"))
    )
    (net (code "150") (name "unconnected-(U10-NC-Pad99)") (class "Default")
      (node (ref "U10") (pin "99") (pinfunction "NC_99") (pintype "no_connect"))
    )
    (net (code "151") (name "unconnected-(U10-NC-Pad100)") (class "Default")
      (node (ref "U10") (pin "100") (pinfunction "NC_100") (pintype "no_connect"))
    )
    (net (code "152") (name "unconnected-(U10-NC-Pad101)") (class "Default")
      (node (ref "U10") (pin "101") (pinfunction "NC_101") (pintype "no_connect"))
    )
    (net (code "153") (name "unconnected-(U10-NC-Pad102)") (class "Default")
      (node (ref "U10") (pin "102") (pinfunction "NC_102") (pintype "no_connect"))
    )
    (net (code "154") (name "unconnected-(U10-NC-Pad103)") (class "Default")
      (node (ref "U10") (pin "103") (pinfunction "NC_103") (pintype "no_connect"))
    )
    (net (code "155") (name "unconnected-(U10-NC-Pad104)") (class "Default")
      (node (ref "U10") (pin "104") (pinfunction "NC_104") (pintype "no_connect"))
    )
    (net (code "156") (name "unconnected-(U10-NC-Pad105)") (class "Default")
      (node (ref "U10") (pin "105") (pinfunction "NC_105") (pintype "no_connect"))
    )
    (net (code "157") (name "unconnected-(U10-NC-Pad106)") (class "Default")
      (node (ref "U10") (pin "106") (pinfunction "NC_106") (pintype "no_connect"))
    )
    (net (code "158") (name "unconnected-(U10-NC-Pad107)") (class "Default")
      (node (ref "U10") (pin "107") (pinfunction "NC_107") (pintype "no_connect"))
    )
    (net (code "159") (name "unconnected-(U10-NC-Pad108)") (class "Default")
      (node (ref "U10") (pin "108") (pinfunction "NC_108") (pintype "no_connect"))
    )
    (net (code "160") (name "unconnected-(U10-NC-Pad109)") (class "Default")
      (node (ref "U10") (pin "109") (pinfunction "NC_109") (pintype "no_connect"))
    )
    (net (code "161") (name "unconnected-(U10-NC-Pad110)") (class "Default")
      (node (ref "U10") (pin "110") (pinfunction "NC_110") (pintype "no_connect"))
    )
    (net (code "162") (name "unconnected-(U10-NC-Pad111)") (class "Default")
      (node (ref "U10") (pin "111") (pinfunction "NC_111") (pintype "no_connect"))
    )
    (net (code "163") (name "unconnected-(U10-NC-Pad112)") (class "Default")
      (node (ref "U10") (pin "112") (pinfunction "NC_112") (pintype "no_connect"))
    )
    (net (code "164") (name "unconnected-(U10-NC-Pad113)") (class "Default")
      (node (ref "U10") (pin "113") (pinfunction "NC_113") (pintype "no_connect"))
    )
    (net (code "165") (name "unconnected-(U10-NC-Pad114)") (class "Default")
      (node (ref "U10") (pin "114") (pinfunction "NC_114") (pintype "no_connect"))
    )
    (net (code "166") (name "unconnected-(U10-NC-Pad115)") (class "Default")
      (node (ref "U10") (pin "115") (pinfunction "NC_115") (pintype "no_connect"))
    )
    (net (code "167") (name "unconnected-(U10-NC-Pad116)") (class "Default")
      (node (ref "U10") (pin "116") (pinfunction "NC_116") (pintype "no_connect"))
    )
    (net (code "168") (name "unconnected-(U10-NC-Pad122)") (class "Default")
      (node (ref "U10") (pin "122") (pinfunction "NC_122") (pintype "no_connect"))
    )
    (net (code "169") (name "unconnected-(U10-TP1_1-Pad74)") (class "Default")
      (node (ref "U10") (pin "74") (pinfunction "TP1_1_74") (pintype "input"))
    )
    (net (code "170") (name "unconnected-(U10-TP1_2-Pad75)") (class "Default")
      (node (ref "U10") (pin "75") (pinfunction "TP1_2_75") (pintype "input"))
    )
    (net (code "171") (name "unconnected-(U14D-OUT-Pad14)") (class "Default")
      (node (ref "U14") (pin "14") (pinfunction "OUT_14") (pintype "output"))
    )
  )
)
